# control.net
KiCad netlist of a schematic drawn in Altium Designer
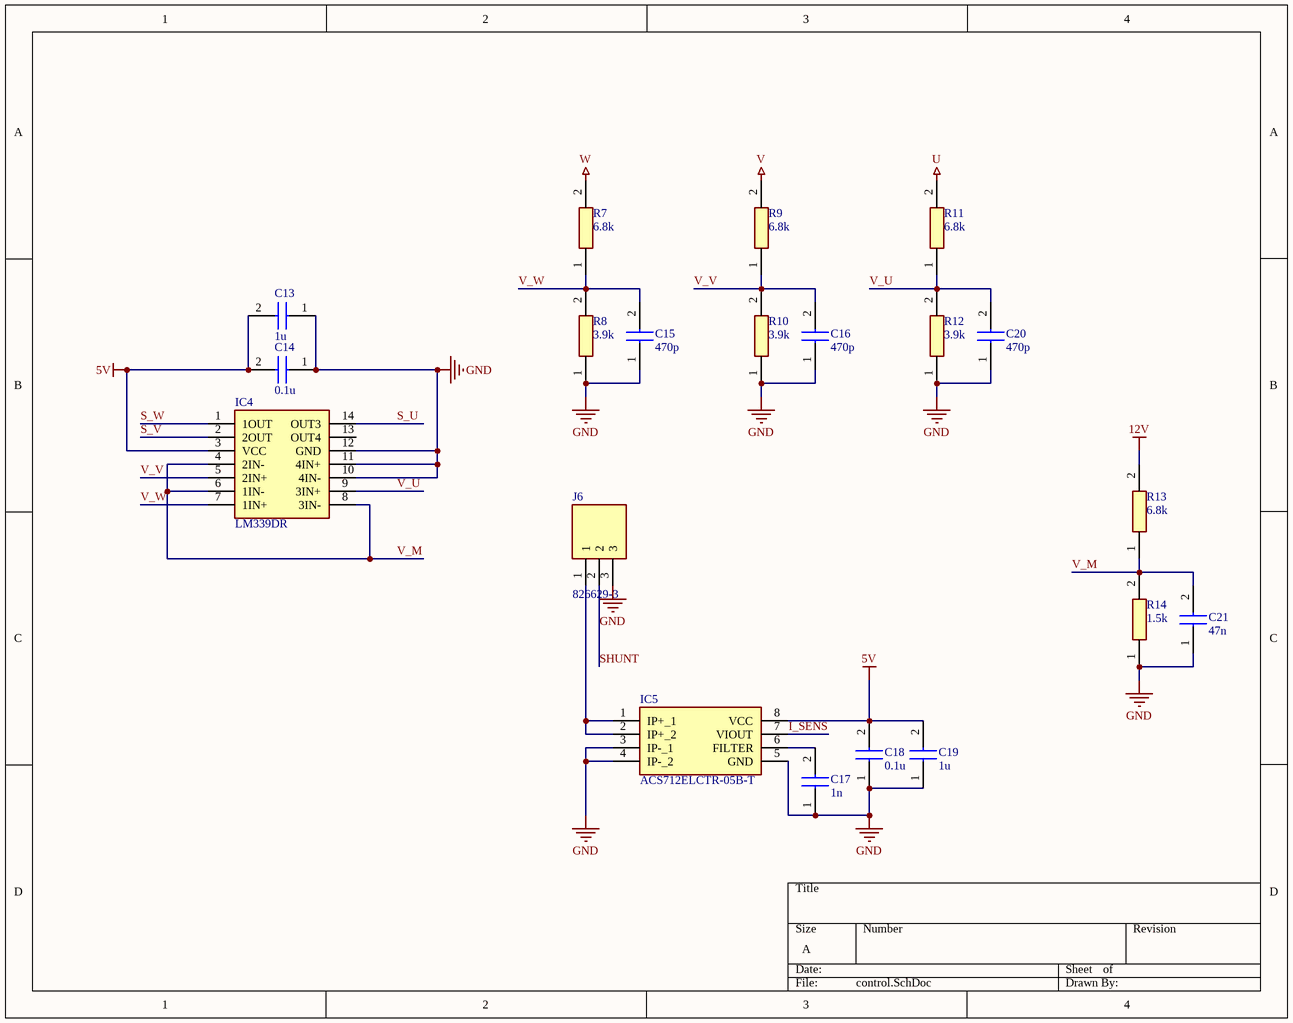
[diagram p0: control.SchDoc]

(export (version "E")
  (design (tool "Eeschema 10.0.6"))
  (components
    (comp (ref "C13")
      (value "1u")
      (footprint "SamacSys:CAPC2012X145N")
      (description "Capacitor")
      (fields
        (field (name "MANUFACTURER_PART_NUMBER") "GRM21BR71C105KA01K")
        (field (name "MOUSER PART NUMBER") "81-GRM40X105K16K")
      )
      (libsource (lib "*") (part "GRM21BR71C105KA01K"))
    )
    (comp (ref "C14")
      (value "0.1u")
      (footprint "SamacSys:CAPC2012X95N")
      (description "Capacitor")
      (fields
        (field (name "MANUFACTURER_PART_NUMBER") "GRM219F51H104ZA01B")
        (field (name "MOUSER PART NUMBER") "81-GRM21F51H104ZA01B")
      )
      (libsource (lib "*") (part "GRM219F51H104ZA01B"))
    )
    (comp (ref "C15")
      (value "470p")
      (footprint "SamacSys:CAPC2012X70N")
      (description "Capacitor")
      (fields
        (field (name "MANUFACTURER_PART_NUMBER") "GRM2165C1H471JA01D")
        (field (name "MOUSER PART NUMBER") "81-GRM215C1H471JA01D")
      )
      (libsource (lib "*") (part "GRM2165C1H471JA01D"))
    )
    (comp (ref "C16")
      (value "470p")
      (footprint "SamacSys:CAPC2012X70N")
      (description "Capacitor")
      (fields
        (field (name "MANUFACTURER_PART_NUMBER") "GRM2165C1H471JA01D")
        (field (name "MOUSER PART NUMBER") "81-GRM215C1H471JA01D")
      )
      (libsource (lib "*") (part "GRM2165C1H471JA01D"))
    )
    (comp (ref "C17")
      (value "1n")
      (footprint "SamacSys:CAPC2012X95N")
      (description "Capacitor")
      (fields
        (field (name "MANUFACTURER_PART_NUMBER") "GRM219F51H104ZA01B")
        (field (name "MOUSER PART NUMBER") "81-GRM21F51H104ZA01B")
      )
      (libsource (lib "*") (part "GRM219F51H104ZA01B"))
    )
    (comp (ref "C18")
      (value "0.1u")
      (footprint "SamacSys:CAPC2012X95N")
      (description "Capacitor")
      (fields
        (field (name "MANUFACTURER_PART_NUMBER") "GRM219F51H104ZA01B")
        (field (name "MOUSER PART NUMBER") "81-GRM21F51H104ZA01B")
      )
      (libsource (lib "*") (part "GRM219F51H104ZA01B"))
    )
    (comp (ref "C19")
      (value "1u")
      (footprint "SamacSys:CAPC2012X145N")
      (description "Capacitor")
      (fields
        (field (name "MANUFACTURER_PART_NUMBER") "GRM21BR71C105KA01K")
        (field (name "MOUSER PART NUMBER") "81-GRM40X105K16K")
      )
      (libsource (lib "*") (part "GRM21BR71C105KA01K"))
    )
    (comp (ref "C20")
      (value "470p")
      (footprint "SamacSys:CAPC2012X70N")
      (description "Capacitor")
      (fields
        (field (name "MANUFACTURER_PART_NUMBER") "GRM2165C1H471JA01D")
        (field (name "MOUSER PART NUMBER") "81-GRM215C1H471JA01D")
      )
      (libsource (lib "*") (part "GRM2165C1H471JA01D"))
    )
    (comp (ref "C21")
      (value "47n")
      (footprint "SamacSys:CAPC2012X70N")
      (description "Capacitor")
      (fields
        (field (name "MANUFACTURER_PART_NUMBER") "GRM2165C1H471JA01D")
        (field (name "MOUSER PART NUMBER") "81-GRM215C1H471JA01D")
      )
      (libsource (lib "*") (part "GRM2165C1H471JA01D"))
    )
    (comp (ref "IC4")
      (value "LM339DR")
      (footprint "SamacSys:SOIC127P600X175-14N")
      (description "Integrated Circuit")
      (fields (field (name "MOUSER PART NUMBER") "595-LM339DR"))
      (libsource (lib "*") (part "LM339DR"))
    )
    (comp (ref "IC5")
      (value "ACS712ELCTR-05B-T")
      (footprint "SamacSys:SOIC127P600X175-8N")
      (description "Integrated Circuit")
      (fields (field (name "MOUSER PART NUMBER") "250-712ELCTR05BT"))
      (libsource (lib "*") (part "ACS712ELCTR-05B-T"))
    )
    (comp (ref "J6")
      (value "826629-3")
      (footprint "SamacSys:HDRV3W63P0X254_1X3_762X250X950P")
      (description "Connector")
      (fields (field (name "MOUSER PART NUMBER") "571-826629-3"))
      (libsource (lib "*") (part "826629-3"))
    )
    (comp (ref "R7")
      (value "6.8k")
      (footprint "SamacSys:RESC2012X60N")
      (description "Resistor")
      (fields
        (field (name "MANUFACTURER_PART_NUMBER") "RC0805FR-076K8L")
        (field (name "MOUSER PART NUMBER") "603-RC0805FR-076K8L")
      )
      (libsource (lib "*") (part "RC0805FR-076K8L"))
    )
    (comp (ref "R8")
      (value "3.9k")
      (footprint "SamacSys:RESC2012X60N")
      (description "Resistor")
      (fields
        (field (name "MANUFACTURER_PART_NUMBER") "RC0805FR-073K9L")
        (field (name "MOUSER PART NUMBER") "603-RC0805FR-073K9L")
      )
      (libsource (lib "*") (part "RC0805FR-073K9L"))
    )
    (comp (ref "R9")
      (value "6.8k")
      (footprint "SamacSys:RESC2012X60N")
      (description "Resistor")
      (fields
        (field (name "MANUFACTURER_PART_NUMBER") "RC0805FR-076K8L")
        (field (name "MOUSER PART NUMBER") "603-RC0805FR-076K8L")
      )
      (libsource (lib "*") (part "RC0805FR-076K8L"))
    )
    (comp (ref "R10")
      (value "3.9k")
      (footprint "SamacSys:RESC2012X60N")
      (description "Resistor")
      (fields
        (field (name "MANUFACTURER_PART_NUMBER") "RC0805FR-073K9L")
        (field (name "MOUSER PART NUMBER") "603-RC0805FR-073K9L")
      )
      (libsource (lib "*") (part "RC0805FR-073K9L"))
    )
    (comp (ref "R11")
      (value "6.8k")
      (footprint "SamacSys:RESC2012X60N")
      (description "Resistor")
      (fields
        (field (name "MANUFACTURER_PART_NUMBER") "RC0805FR-076K8L")
        (field (name "MOUSER PART NUMBER") "603-RC0805FR-076K8L")
      )
      (libsource (lib "*") (part "RC0805FR-076K8L"))
    )
    (comp (ref "R12")
      (value "3.9k")
      (footprint "SamacSys:RESC2012X60N")
      (description "Resistor")
      (fields
        (field (name "MANUFACTURER_PART_NUMBER") "RC0805FR-073K9L")
        (field (name "MOUSER PART NUMBER") "603-RC0805FR-073K9L")
      )
      (libsource (lib "*") (part "RC0805FR-073K9L"))
    )
    (comp (ref "R13")
      (value "6.8k")
      (footprint "SamacSys:RESC2012X60N")
      (description "Resistor")
      (fields
        (field (name "MANUFACTURER_PART_NUMBER") "RC0805FR-076K8L")
        (field (name "MOUSER PART NUMBER") "603-RC0805FR-076K8L")
      )
      (libsource (lib "*") (part "RC0805FR-076K8L"))
    )
    (comp (ref "R14")
      (value "1.5k")
      (footprint "SamacSys:RESC2012X60N")
      (description "Resistor")
      (fields
        (field (name "MANUFACTURER_PART_NUMBER") "RC0805FR-071K5L")
        (field (name "MOUSER PART NUMBER") "603-RC0805FR-071K5L")
      )
      (libsource (lib "*") (part "RC0805FR-071K5L"))
    )
  )
  (nets
    (net (code "1") (name "/I_SENS") (class "Default")
      (node (ref "IC5") (pin "7") (pinfunction "VIOUT_7") (pintype "passive"))
    )
    (net (code "2") (name "/SHUNT") (class "Default")
      (node (ref "J6") (pin "2") (pinfunction "2_2") (pintype "passive"))
    )
    (net (code "3") (name "/S_U") (class "Default")
      (node (ref "IC4") (pin "14") (pinfunction "OUT3_14") (pintype "passive"))
    )
    (net (code "4") (name "/S_V") (class "Default")
      (node (ref "IC4") (pin "2") (pinfunction "2OUT_2") (pintype "passive"))
    )
    (net (code "5") (name "/S_W") (class "Default")
      (node (ref "IC4") (pin "1") (pinfunction "1OUT_1") (pintype "passive"))
    )
    (net (code "6") (name "/V_M") (class "Default")
      (node (ref "C21") (pin "2") (pinfunction "2_2") (pintype "passive"))
      (node (ref "IC4") (pin "4") (pinfunction "2IN-_4") (pintype "passive"))
      (node (ref "IC4") (pin "6") (pinfunction "1IN-_6") (pintype "passive"))
      (node (ref "IC4") (pin "8") (pinfunction "3IN-_8") (pintype "passive"))
      (node (ref "R13") (pin "1") (pinfunction "1_1") (pintype "passive"))
      (node (ref "R14") (pin "2") (pinfunction "2_2") (pintype "passive"))
    )
    (net (code "7") (name "/V_U") (class "Default")
      (node (ref "C20") (pin "2") (pinfunction "2_2") (pintype "passive"))
      (node (ref "IC4") (pin "9") (pinfunction "3IN+_9") (pintype "passive"))
      (node (ref "R11") (pin "1") (pinfunction "1_1") (pintype "passive"))
      (node (ref "R12") (pin "2") (pinfunction "2_2") (pintype "passive"))
    )
    (net (code "8") (name "/V_V") (class "Default")
      (node (ref "C16") (pin "2") (pinfunction "2_2") (pintype "passive"))
      (node (ref "IC4") (pin "5") (pinfunction "2IN+_5") (pintype "passive"))
      (node (ref "R10") (pin "2") (pinfunction "2_2") (pintype "passive"))
      (node (ref "R9") (pin "1") (pinfunction "1_1") (pintype "passive"))
    )
    (net (code "9") (name "/V_W") (class "Default")
      (node (ref "C15") (pin "2") (pinfunction "2_2") (pintype "passive"))
      (node (ref "IC4") (pin "7") (pinfunction "1IN+_7") (pintype "passive"))
      (node (ref "R7") (pin "1") (pinfunction "1_1") (pintype "passive"))
      (node (ref "R8") (pin "2") (pinfunction "2_2") (pintype "passive"))
    )
    (net (code "10") (name "5V") (class "Default")
      (node (ref "C13") (pin "2") (pinfunction "2_2") (pintype "passive"))
      (node (ref "C14") (pin "2") (pinfunction "2_2") (pintype "passive"))
      (node (ref "C18") (pin "2") (pinfunction "2_2") (pintype "passive"))
      (node (ref "C19") (pin "2") (pinfunction "2_2") (pintype "passive"))
      (node (ref "IC4") (pin "3") (pinfunction "VCC_3") (pintype "passive"))
      (node (ref "IC5") (pin "8") (pinfunction "VCC_8") (pintype "passive"))
    )
    (net (code "11") (name "12V") (class "Default")
      (node (ref "R13") (pin "2") (pinfunction "2_2") (pintype "passive"))
    )
    (net (code "12") (name "GND") (class "Default")
      (node (ref "C13") (pin "1") (pinfunction "1_1") (pintype "passive"))
      (node (ref "C14") (pin "1") (pinfunction "1_1") (pintype "passive"))
      (node (ref "C15") (pin "1") (pinfunction "1_1") (pintype "passive"))
      (node (ref "C16") (pin "1") (pinfunction "1_1") (pintype "passive"))
      (node (ref "C17") (pin "1") (pinfunction "1_1") (pintype "passive"))
      (node (ref "C18") (pin "1") (pinfunction "1_1") (pintype "passive"))
      (node (ref "C19") (pin "1") (pinfunction "1_1") (pintype "passive"))
      (node (ref "C20") (pin "1") (pinfunction "1_1") (pintype "passive"))
      (node (ref "C21") (pin "1") (pinfunction "1_1") (pintype "passive"))
      (node (ref "IC4") (pin "10") (pinfunction "4IN-_10") (pintype "passive"))
      (node (ref "IC4") (pin "11") (pinfunction "4IN+_11") (pintype "passive"))
      (node (ref "IC4") (pin "12") (pinfunction "GND_12") (pintype "passive"))
      (node (ref "IC5") (pin "3") (pinfunction "IP-_1_3") (pintype "passive"))
      (node (ref "IC5") (pin "4") (pinfunction "IP-_2_4") (pintype "passive"))
      (node (ref "IC5") (pin "5") (pinfunction "GND_5") (pintype "passive"))
      (node (ref "J6") (pin "3") (pinfunction "3_3") (pintype "passive"))
      (node (ref "R10") (pin "1") (pinfunction "1_1") (pintype "passive"))
      (node (ref "R12") (pin "1") (pinfunction "1_1") (pintype "passive"))
      (node (ref "R14") (pin "1") (pinfunction "1_1") (pintype "passive"))
      (node (ref "R8") (pin "1") (pinfunction "1_1") (pintype "passive"))
    )
    (net (code "13") (name "Net-(IC5-FILTER)") (class "Default")
      (node (ref "C17") (pin "2") (pinfunction "2_2") (pintype "passive"))
      (node (ref "IC5") (pin "6") (pinfunction "FILTER_6") (pintype "passive"))
    )
    (net (code "14") (name "Net-(IC5-IP+_1)") (class "Default")
      (node (ref "IC5") (pin "1") (pinfunction "IP+_1_1") (pintype "passive"))
      (node (ref "IC5") (pin "2") (pinfunction "IP+_2_2") (pintype "passive"))
      (node (ref "J6") (pin "1") (pinfunction "1_1") (pintype "passive"))
    )
    (net (code "15") (name "U") (class "Default")
      (node (ref "R11") (pin "2") (pinfunction "2_2") (pintype "passive"))
    )
    (net (code "16") (name "V") (class "Default")
      (node (ref "R9") (pin "2") (pinfunction "2_2") (pintype "passive"))
    )
    (net (code "17") (name "W") (class "Default")
      (node (ref "R7") (pin "2") (pinfunction "2_2") (pintype "passive"))
    )
    (net (code "18") (name "unconnected-(IC4-OUT4-Pad13)") (class "Default")
      (node (ref "IC4") (pin "13") (pinfunction "OUT4_13") (pintype "passive"))
    )
  )
)
